# Antenna_matching_circuit.net
KiCad netlist of a schematic drawn in Altium Designer
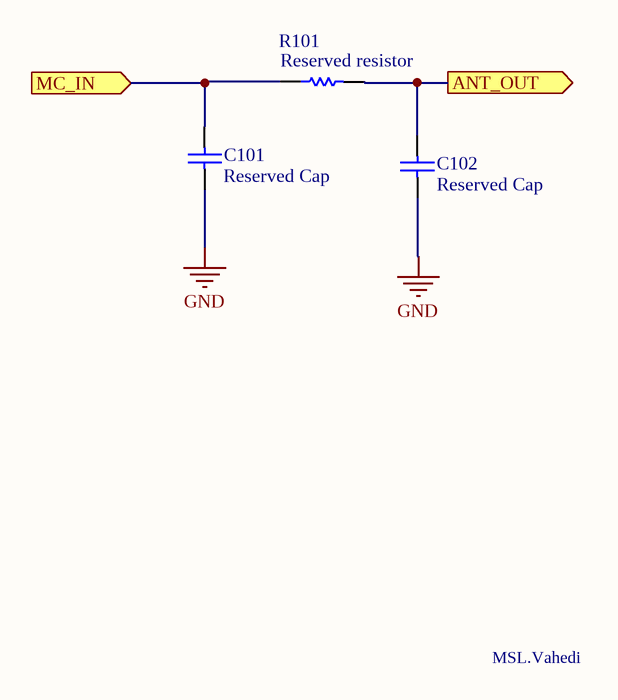
[diagram p0: Antenna matching circuit.SchDoc]

(export (version "E")
  (design (tool "Eeschema 10.0.6"))
  (components
    (comp (ref "C101")
      (value "Reserved Cap")
      (footprint "CAP0805")
      (description "Capacitor")
      (fields (field (name "PUBLISHER") "Altium Limited"))
      (libsource (lib "Miscellaneous Devices") (part "Cap"))
    )
    (comp (ref "C102")
      (value "Reserved Cap")
      (footprint "CAP0805")
      (description "Capacitor")
      (fields (field (name "PUBLISHER") "Altium Limited"))
      (libsource (lib "Miscellaneous Devices") (part "Cap"))
    )
    (comp (ref "R101")
      (value "Reserved resistor")
      (footprint "RES0805")
      (description "Resistor")
      (fields (field (name "PUBLISHER") "Altium Limited"))
      (libsource (lib "Miscellaneous Devices") (part "Res1"))
    )
  )
  (nets
    (net (code "1") (name "/ANT_OUT") (class "Default")
      (node (ref "C102") (pin "2") (pinfunction "2_2") (pintype "passive"))
      (node (ref "R101") (pin "2") (pinfunction "2_2") (pintype "passive"))
    )
    (net (code "2") (name "/MC_IN") (class "Default")
      (node (ref "C101") (pin "2") (pinfunction "2_2") (pintype "passive"))
      (node (ref "R101") (pin "1") (pinfunction "1_1") (pintype "passive"))
    )
    (net (code "3") (name "GND") (class "Default")
      (node (ref "C101") (pin "1") (pinfunction "1_1") (pintype "passive"))
      (node (ref "C102") (pin "1") (pinfunction "1_1") (pintype "passive"))
    )
  )
)
